# 2s-lvco.net
KiCad netlist of a schematic drawn in EAGLE
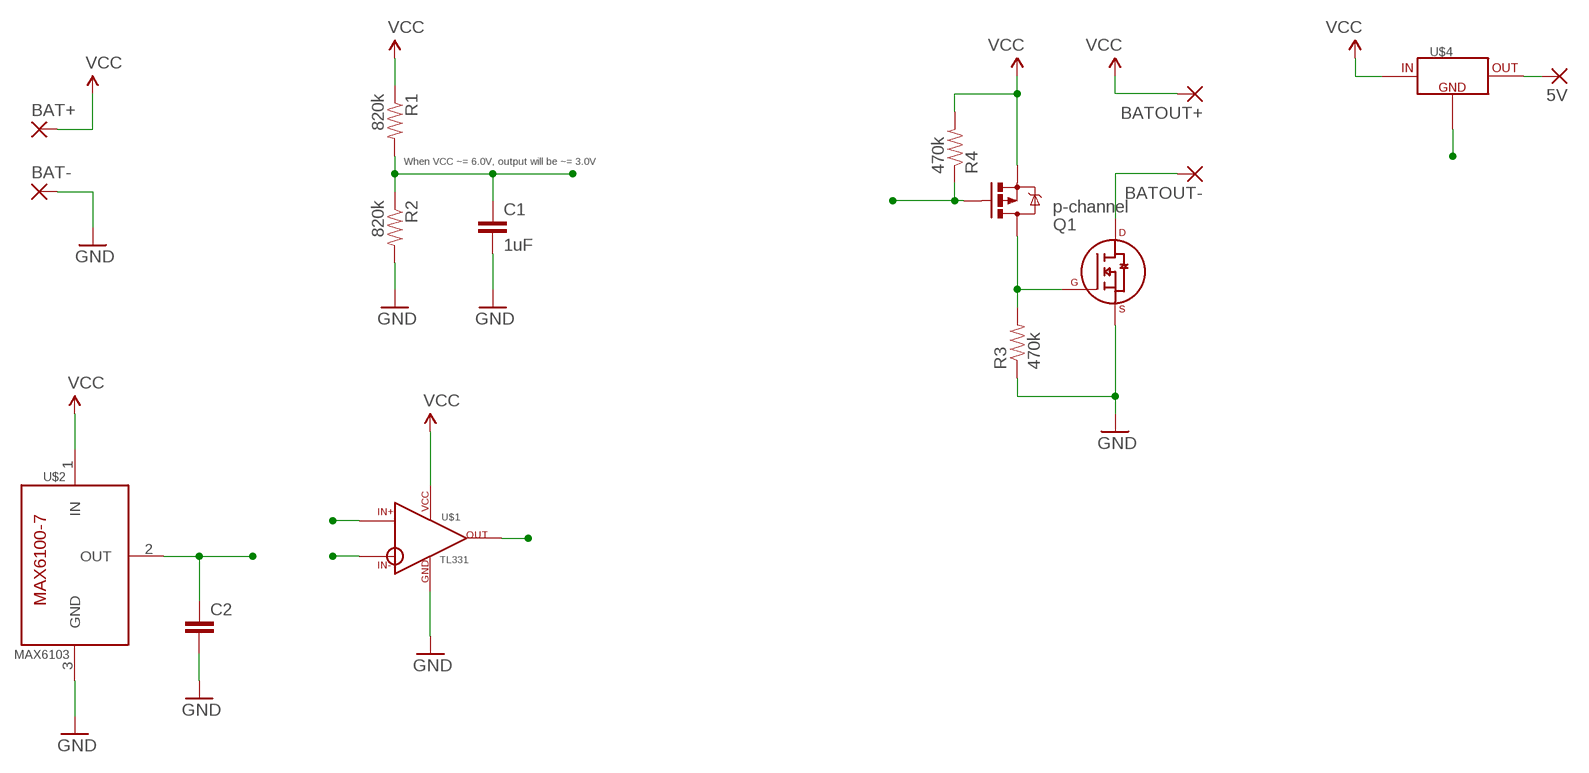
[diagram p0: schematic, sheet 1]

(export (version "E")
  (design (tool "Eeschema 10.0.6"))
  (components
    (comp (ref "5V")
      (value "WIREPADSMD2,54-5,08")
      (footprint "eagle-import:SMD2,54-5,08")
      (libsource (lib "eagle-import") (part "WIREPADSMD2,54-5,08"))
    )
    (comp (ref "BAT+")
      (value "WIREPADSMD2,54-5,08")
      (footprint "eagle-import:SMD2,54-5,08")
      (libsource (lib "eagle-import") (part "WIREPADSMD2,54-5,08"))
    )
    (comp (ref "BAT-")
      (value "WIREPADSMD2,54-5,08")
      (footprint "eagle-import:SMD2,54-5,08")
      (libsource (lib "eagle-import") (part "WIREPADSMD2,54-5,08"))
    )
    (comp (ref "BATOUT+")
      (value "WIREPADSMD2,54-5,08")
      (footprint "eagle-import:SMD2,54-5,08")
      (libsource (lib "eagle-import") (part "WIREPADSMD2,54-5,08"))
    )
    (comp (ref "BATOUT-")
      (value "WIREPADSMD2,54-5,08")
      (footprint "eagle-import:SMD2,54-5,08")
      (libsource (lib "eagle-import") (part "WIREPADSMD2,54-5,08"))
    )
    (comp (ref "C1")
      (value "1uF")
      (footprint "eagle-import:0603-CAP")
      (libsource (lib "eagle-import") (part "CAP0603-CAP"))
    )
    (comp (ref "C2")
      (value "CAP0603-CAP")
      (footprint "eagle-import:0603-CAP")
      (libsource (lib "eagle-import") (part "CAP0603-CAP"))
    )
    (comp (ref "Q1")
      (value "p-channel")
      (footprint "eagle-import:SOT23-3")
      (libsource (lib "eagle-import") (part "MOSFET-PCHANNELSMD"))
    )
    (comp (ref "R1")
      (value "820k")
      (footprint "eagle-import:0603-RES")
      (libsource (lib "eagle-import") (part "RESISTOR0603-RES"))
    )
    (comp (ref "R2")
      (value "820k")
      (footprint "eagle-import:0603-RES")
      (libsource (lib "eagle-import") (part "RESISTOR0603-RES"))
    )
    (comp (ref "R3")
      (value "470k")
      (footprint "eagle-import:0603-RES")
      (libsource (lib "eagle-import") (part "RESISTOR0603-RES"))
    )
    (comp (ref "R4")
      (value "470k")
      (footprint "eagle-import:0603-RES")
      (libsource (lib "eagle-import") (part "RESISTOR0603-RES"))
    )
    (comp (ref "U$1")
      (value "TL331")
      (footprint "eagle-import:SOT-23-5")
      (libsource (lib "eagle-import") (part "TL331"))
    )
    (comp (ref "U$2")
      (value "MAX6103")
      (footprint "eagle-import:SOT-23-3")
      (libsource (lib "eagle-import") (part "MAX6100-MAX6107"))
    )
    (comp (ref "U$3")
      (value "RFD14N05L")
      (footprint "eagle-import:TO-252AA")
      (libsource (lib "eagle-import") (part "RFD14N05L"))
    )
    (comp (ref "U$4")
      (value "TPS715XX")
      (footprint "eagle-import:SOT-23-5")
      (libsource (lib "eagle-import") (part "TPS715XX"))
    )
  )
  (nets
    (net (code "1") (name "/BATOUT-") (class "Default")
      (node (ref "BATOUT-") (pin "1") (pinfunction "P_1") (pintype "passive"))
      (node (ref "U$3") (pin "4") (pinfunction "D_4") (pintype "bidirectional"))
      (node (ref "U$4") (pin "2") (pinfunction "GND_2") (pintype "bidirectional"))
    )
    (net (code "2") (name "/REF") (class "Default")
      (node (ref "C2") (pin "1") (pinfunction "1_1") (pintype "passive"))
      (node (ref "U$1") (pin "3") (pinfunction "IN+_3") (pintype "bidirectional"))
      (node (ref "U$2") (pin "2") (pinfunction "OUT_2") (pintype "bidirectional"))
    )
    (net (code "3") (name "/SW") (class "Default")
      (node (ref "Q1") (pin "1") (pinfunction "G_1") (pintype "passive"))
      (node (ref "R4") (pin "1") (pinfunction "1_1") (pintype "passive"))
      (node (ref "U$1") (pin "4") (pinfunction "OUT_4") (pintype "bidirectional"))
    )
    (net (code "4") (name "/VDIV_OUT") (class "Default")
      (node (ref "C1") (pin "1") (pinfunction "1_1") (pintype "passive"))
      (node (ref "R1") (pin "2") (pinfunction "2_2") (pintype "passive"))
      (node (ref "R2") (pin "1") (pinfunction "1_1") (pintype "passive"))
      (node (ref "U$1") (pin "1") (pinfunction "IN-_1") (pintype "bidirectional"))
    )
    (net (code "5") (name "GND") (class "Default")
      (node (ref "BAT-") (pin "1") (pinfunction "P_1") (pintype "passive"))
      (node (ref "C1") (pin "2") (pinfunction "2_2") (pintype "passive"))
      (node (ref "C2") (pin "2") (pinfunction "2_2") (pintype "passive"))
      (node (ref "R2") (pin "2") (pinfunction "2_2") (pintype "passive"))
      (node (ref "R3") (pin "1") (pinfunction "1_1") (pintype "passive"))
      (node (ref "U$1") (pin "2") (pinfunction "GND_2") (pintype "bidirectional"))
      (node (ref "U$2") (pin "3") (pinfunction "GND_3") (pintype "bidirectional"))
      (node (ref "U$3") (pin "3") (pinfunction "S_3") (pintype "bidirectional"))
    )
    (net (code "6") (name "Net-(5V-P)") (class "Default")
      (node (ref "5V") (pin "1") (pinfunction "P_1") (pintype "passive"))
      (node (ref "U$4") (pin "5") (pinfunction "OUT_5") (pintype "bidirectional"))
    )
    (net (code "7") (name "Net-(Q1-D)") (class "Default")
      (node (ref "Q1") (pin "3") (pinfunction "D_3") (pintype "passive"))
      (node (ref "R3") (pin "2") (pinfunction "2_2") (pintype "passive"))
      (node (ref "U$3") (pin "1") (pinfunction "G_1") (pintype "bidirectional"))
    )
    (net (code "8") (name "VCC") (class "Default")
      (node (ref "BAT+") (pin "1") (pinfunction "P_1") (pintype "passive"))
      (node (ref "BATOUT+") (pin "1") (pinfunction "P_1") (pintype "passive"))
      (node (ref "Q1") (pin "2") (pinfunction "S_2") (pintype "passive"))
      (node (ref "R1") (pin "1") (pinfunction "1_1") (pintype "passive"))
      (node (ref "R4") (pin "2") (pinfunction "2_2") (pintype "passive"))
      (node (ref "U$1") (pin "5") (pinfunction "VCC_5") (pintype "bidirectional"))
      (node (ref "U$2") (pin "1") (pinfunction "IN_1") (pintype "bidirectional"))
      (node (ref "U$4") (pin "4") (pinfunction "IN_4") (pintype "bidirectional"))
    )
  )
)
